# nano24rf.net
KiCad netlist of a schematic drawn in EAGLE
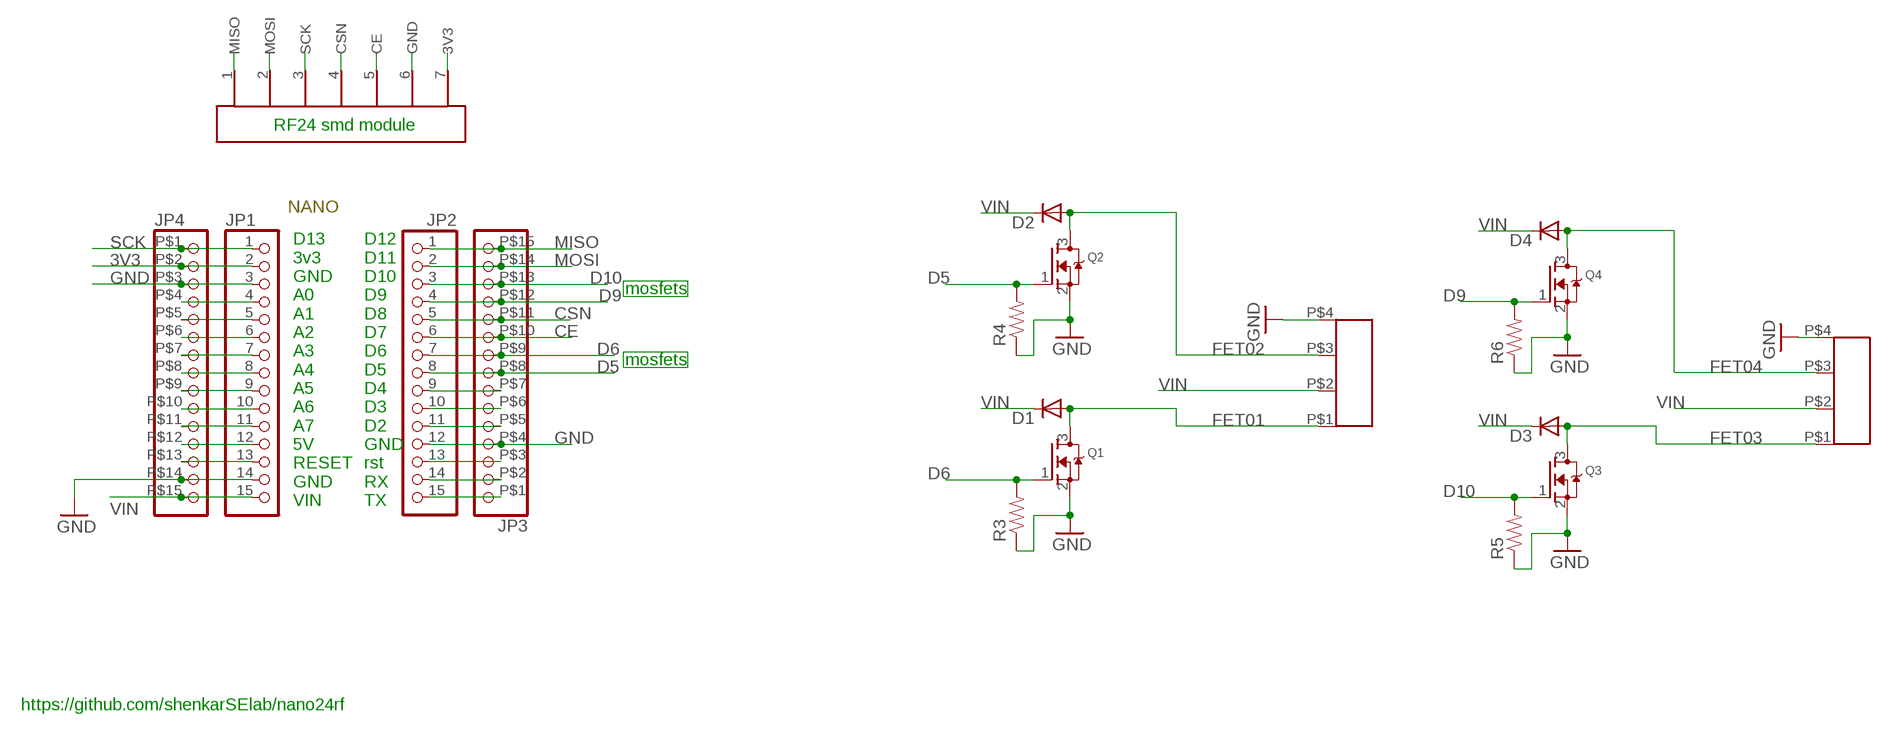
[diagram p0: schematic, sheet 1]

(export (version "E")
  (design (tool "Eeschema 10.0.6"))
  (components
    (comp (ref "D1")
      (value "DIODE-DO-214AC")
      (footprint "eagle-import:DO-214AC")
      (libsource (lib "eagle-import") (part "DIODE-DO-214AC"))
    )
    (comp (ref "D2")
      (value "DIODE-DO-214AC")
      (footprint "eagle-import:DO-214AC")
      (libsource (lib "eagle-import") (part "DIODE-DO-214AC"))
    )
    (comp (ref "D3")
      (value "DIODE-DO-214AC")
      (footprint "eagle-import:DO-214AC")
      (libsource (lib "eagle-import") (part "DIODE-DO-214AC"))
    )
    (comp (ref "D4")
      (value "DIODE-DO-214AC")
      (footprint "eagle-import:DO-214AC")
      (libsource (lib "eagle-import") (part "DIODE-DO-214AC"))
    )
    (comp (ref "JP1")
      (value "HEADER-1X15RND")
      (footprint "eagle-import:1X15_ROUND_70")
      (libsource (lib "eagle-import") (part "HEADER-1X15RND"))
    )
    (comp (ref "JP2")
      (value "HEADER-1X15RND")
      (footprint "eagle-import:1X15_ROUND_70")
      (libsource (lib "eagle-import") (part "HEADER-1X15RND"))
    )
    (comp (ref "JP3")
      (value "HEADER-1X15LONG")
      (footprint "eagle-import:1X15_LONG")
      (libsource (lib "eagle-import") (part "HEADER-1X15LONG"))
    )
    (comp (ref "JP4")
      (value "HEADER-1X15LONG")
      (footprint "eagle-import:1X15_LONG")
      (libsource (lib "eagle-import") (part "HEADER-1X15LONG"))
    )
    (comp (ref "MOSFET-12")
      (value "FATPAD4LONG")
      (footprint "eagle-import:FATFAD4-LONG")
      (libsource (lib "eagle-import") (part "FATPAD4LONG"))
    )
    (comp (ref "MOSFET-34")
      (value "FATPAD4LONG")
      (footprint "eagle-import:FATFAD4-LONG")
      (libsource (lib "eagle-import") (part "FATPAD4LONG"))
    )
    (comp (ref "Q1")
      (value "MOSFET-NWAVE")
      (footprint "eagle-import:SOT23-W")
      (libsource (lib "eagle-import") (part "MOSFET-NWAVE"))
    )
    (comp (ref "Q2")
      (value "MOSFET-NWAVE")
      (footprint "eagle-import:SOT23-W")
      (libsource (lib "eagle-import") (part "MOSFET-NWAVE"))
    )
    (comp (ref "Q3")
      (value "MOSFET-NWAVE")
      (footprint "eagle-import:SOT23-W")
      (libsource (lib "eagle-import") (part "MOSFET-NWAVE"))
    )
    (comp (ref "Q4")
      (value "MOSFET-NWAVE")
      (footprint "eagle-import:SOT23-W")
      (libsource (lib "eagle-import") (part "MOSFET-NWAVE"))
    )
    (comp (ref "R3")
      (value "RESISTOR0805-RES")
      (footprint "eagle-import:0805")
      (libsource (lib "eagle-import") (part "RESISTOR0805-RES"))
    )
    (comp (ref "R4")
      (value "RESISTOR0805-RES")
      (footprint "eagle-import:0805")
      (libsource (lib "eagle-import") (part "RESISTOR0805-RES"))
    )
    (comp (ref "R5")
      (value "RESISTOR0805-RES")
      (footprint "eagle-import:0805")
      (libsource (lib "eagle-import") (part "RESISTOR0805-RES"))
    )
    (comp (ref "R6")
      (value "RESISTOR0805-RES")
      (footprint "eagle-import:0805")
      (libsource (lib "eagle-import") (part "RESISTOR0805-RES"))
    )
    (comp (ref "RF24")
      (value "1X7-SMDPADS")
      (footprint "eagle-import:SMD1,27-2,54")
      (libsource (lib "eagle-import") (part "1X7-SMDPADS"))
    )
  )
  (nets
    (net (code "1") (name "3V3") (class "Default")
      (node (ref "JP1") (pin "2") (pinfunction "2_2") (pintype "passive"))
      (node (ref "JP4") (pin "P$2") (pinfunction "2_P$2") (pintype "passive"))
      (node (ref "RF24") (pin "7") (pinfunction "3V3_7") (pintype "bidirectional"))
    )
    (net (code "2") (name "CE") (class "Default")
      (node (ref "JP2") (pin "6") (pinfunction "6_6") (pintype "passive"))
      (node (ref "JP3") (pin "P$10") (pinfunction "10_P$10") (pintype "passive"))
      (node (ref "RF24") (pin "5") (pinfunction "CE_5") (pintype "bidirectional"))
    )
    (net (code "3") (name "CSN") (class "Default")
      (node (ref "JP2") (pin "5") (pinfunction "5_5") (pintype "passive"))
      (node (ref "JP3") (pin "P$11") (pinfunction "11_P$11") (pintype "passive"))
      (node (ref "RF24") (pin "4") (pinfunction "CSN_4") (pintype "bidirectional"))
    )
    (net (code "4") (name "D5") (class "Default")
      (node (ref "JP2") (pin "8") (pinfunction "8_8") (pintype "passive"))
      (node (ref "JP3") (pin "P$8") (pinfunction "8_P$8") (pintype "passive"))
      (node (ref "Q2") (pin "1") (pinfunction "G_1") (pintype "bidirectional"))
      (node (ref "R4") (pin "2") (pinfunction "2_2") (pintype "passive"))
    )
    (net (code "5") (name "D6") (class "Default")
      (node (ref "JP2") (pin "7") (pinfunction "7_7") (pintype "passive"))
      (node (ref "JP3") (pin "P$9") (pinfunction "9_P$9") (pintype "passive"))
      (node (ref "Q1") (pin "1") (pinfunction "G_1") (pintype "bidirectional"))
      (node (ref "R3") (pin "2") (pinfunction "2_2") (pintype "passive"))
    )
    (net (code "6") (name "D9") (class "Default")
      (node (ref "JP2") (pin "4") (pinfunction "4_4") (pintype "passive"))
      (node (ref "JP3") (pin "P$12") (pinfunction "12_P$12") (pintype "passive"))
      (node (ref "Q4") (pin "1") (pinfunction "G_1") (pintype "bidirectional"))
      (node (ref "R6") (pin "2") (pinfunction "2_2") (pintype "passive"))
    )
    (net (code "7") (name "D10") (class "Default")
      (node (ref "JP2") (pin "3") (pinfunction "3_3") (pintype "passive"))
      (node (ref "JP3") (pin "P$13") (pinfunction "13_P$13") (pintype "passive"))
      (node (ref "Q3") (pin "1") (pinfunction "G_1") (pintype "bidirectional"))
      (node (ref "R5") (pin "2") (pinfunction "2_2") (pintype "passive"))
    )
    (net (code "8") (name "FET01") (class "Default")
      (node (ref "D1") (pin "2") (pinfunction "A_2") (pintype "passive"))
      (node (ref "MOSFET-12") (pin "P$1") (pinfunction "P$1_P$1") (pintype "bidirectional"))
      (node (ref "Q1") (pin "3") (pinfunction "D_3") (pintype "bidirectional"))
    )
    (net (code "9") (name "FET02") (class "Default")
      (node (ref "D2") (pin "2") (pinfunction "A_2") (pintype "passive"))
      (node (ref "MOSFET-12") (pin "P$3") (pinfunction "P$3_P$3") (pintype "bidirectional"))
      (node (ref "Q2") (pin "3") (pinfunction "D_3") (pintype "bidirectional"))
    )
    (net (code "10") (name "FET03") (class "Default")
      (node (ref "D3") (pin "2") (pinfunction "A_2") (pintype "passive"))
      (node (ref "MOSFET-34") (pin "P$1") (pinfunction "P$1_P$1") (pintype "bidirectional"))
      (node (ref "Q3") (pin "3") (pinfunction "D_3") (pintype "bidirectional"))
    )
    (net (code "11") (name "FET04") (class "Default")
      (node (ref "D4") (pin "2") (pinfunction "A_2") (pintype "passive"))
      (node (ref "MOSFET-34") (pin "P$3") (pinfunction "P$3_P$3") (pintype "bidirectional"))
      (node (ref "Q4") (pin "3") (pinfunction "D_3") (pintype "bidirectional"))
    )
    (net (code "12") (name "GND") (class "Default")
      (node (ref "JP1") (pin "14") (pinfunction "14_14") (pintype "passive"))
      (node (ref "JP1") (pin "3") (pinfunction "3_3") (pintype "passive"))
      (node (ref "JP2") (pin "12") (pinfunction "12_12") (pintype "passive"))
      (node (ref "JP3") (pin "P$4") (pinfunction "4_P$4") (pintype "passive"))
      (node (ref "JP4") (pin "P$14") (pinfunction "14_P$14") (pintype "passive"))
      (node (ref "JP4") (pin "P$3") (pinfunction "3_P$3") (pintype "passive"))
      (node (ref "MOSFET-12") (pin "P$4") (pinfunction "P$4_P$4") (pintype "bidirectional"))
      (node (ref "MOSFET-34") (pin "P$4") (pinfunction "P$4_P$4") (pintype "bidirectional"))
      (node (ref "Q1") (pin "2") (pinfunction "S_2") (pintype "bidirectional"))
      (node (ref "Q2") (pin "2") (pinfunction "S_2") (pintype "bidirectional"))
      (node (ref "Q3") (pin "2") (pinfunction "S_2") (pintype "bidirectional"))
      (node (ref "Q4") (pin "2") (pinfunction "S_2") (pintype "bidirectional"))
      (node (ref "R3") (pin "1") (pinfunction "1_1") (pintype "passive"))
      (node (ref "R4") (pin "1") (pinfunction "1_1") (pintype "passive"))
      (node (ref "R5") (pin "1") (pinfunction "1_1") (pintype "passive"))
      (node (ref "R6") (pin "1") (pinfunction "1_1") (pintype "passive"))
      (node (ref "RF24") (pin "6") (pinfunction "GND_6") (pintype "bidirectional"))
    )
    (net (code "13") (name "MISO") (class "Default")
      (node (ref "JP2") (pin "1") (pinfunction "1_1") (pintype "passive"))
      (node (ref "JP3") (pin "P$15") (pinfunction "15_P$15") (pintype "passive"))
      (node (ref "RF24") (pin "1") (pinfunction "MISO_1") (pintype "bidirectional"))
    )
    (net (code "14") (name "MOSI") (class "Default")
      (node (ref "JP2") (pin "2") (pinfunction "2_2") (pintype "passive"))
      (node (ref "JP3") (pin "P$14") (pinfunction "14_P$14") (pintype "passive"))
      (node (ref "RF24") (pin "2") (pinfunction "MOSI_2") (pintype "bidirectional"))
    )
    (net (code "15") (name "Net-(JP3-1)") (class "Default")
      (node (ref "JP2") (pin "15") (pinfunction "15_15") (pintype "passive"))
      (node (ref "JP3") (pin "P$1") (pinfunction "1_P$1") (pintype "passive"))
    )
    (net (code "16") (name "Net-(JP3-2)") (class "Default")
      (node (ref "JP2") (pin "14") (pinfunction "14_14") (pintype "passive"))
      (node (ref "JP3") (pin "P$2") (pinfunction "2_P$2") (pintype "passive"))
    )
    (net (code "17") (name "Net-(JP3-3)") (class "Default")
      (node (ref "JP2") (pin "13") (pinfunction "13_13") (pintype "passive"))
      (node (ref "JP3") (pin "P$3") (pinfunction "3_P$3") (pintype "passive"))
    )
    (net (code "18") (name "Net-(JP3-5)") (class "Default")
      (node (ref "JP2") (pin "11") (pinfunction "11_11") (pintype "passive"))
      (node (ref "JP3") (pin "P$5") (pinfunction "5_P$5") (pintype "passive"))
    )
    (net (code "19") (name "Net-(JP3-6)") (class "Default")
      (node (ref "JP2") (pin "10") (pinfunction "10_10") (pintype "passive"))
      (node (ref "JP3") (pin "P$6") (pinfunction "6_P$6") (pintype "passive"))
    )
    (net (code "20") (name "Net-(JP3-7)") (class "Default")
      (node (ref "JP2") (pin "9") (pinfunction "9_9") (pintype "passive"))
      (node (ref "JP3") (pin "P$7") (pinfunction "7_P$7") (pintype "passive"))
    )
    (net (code "21") (name "Net-(JP4-4)") (class "Default")
      (node (ref "JP1") (pin "4") (pinfunction "4_4") (pintype "passive"))
      (node (ref "JP4") (pin "P$4") (pinfunction "4_P$4") (pintype "passive"))
    )
    (net (code "22") (name "Net-(JP4-5)") (class "Default")
      (node (ref "JP1") (pin "5") (pinfunction "5_5") (pintype "passive"))
      (node (ref "JP4") (pin "P$5") (pinfunction "5_P$5") (pintype "passive"))
    )
    (net (code "23") (name "Net-(JP4-6)") (class "Default")
      (node (ref "JP1") (pin "6") (pinfunction "6_6") (pintype "passive"))
      (node (ref "JP4") (pin "P$6") (pinfunction "6_P$6") (pintype "passive"))
    )
    (net (code "24") (name "Net-(JP4-7)") (class "Default")
      (node (ref "JP1") (pin "7") (pinfunction "7_7") (pintype "passive"))
      (node (ref "JP4") (pin "P$7") (pinfunction "7_P$7") (pintype "passive"))
    )
    (net (code "25") (name "Net-(JP4-8)") (class "Default")
      (node (ref "JP1") (pin "8") (pinfunction "8_8") (pintype "passive"))
      (node (ref "JP4") (pin "P$8") (pinfunction "8_P$8") (pintype "passive"))
    )
    (net (code "26") (name "Net-(JP4-9)") (class "Default")
      (node (ref "JP1") (pin "9") (pinfunction "9_9") (pintype "passive"))
      (node (ref "JP4") (pin "P$9") (pinfunction "9_P$9") (pintype "passive"))
    )
    (net (code "27") (name "Net-(JP4-10)") (class "Default")
      (node (ref "JP1") (pin "10") (pinfunction "10_10") (pintype "passive"))
      (node (ref "JP4") (pin "P$10") (pinfunction "10_P$10") (pintype "passive"))
    )
    (net (code "28") (name "Net-(JP4-11)") (class "Default")
      (node (ref "JP1") (pin "11") (pinfunction "11_11") (pintype "passive"))
      (node (ref "JP4") (pin "P$11") (pinfunction "11_P$11") (pintype "passive"))
    )
    (net (code "29") (name "Net-(JP4-12)") (class "Default")
      (node (ref "JP1") (pin "12") (pinfunction "12_12") (pintype "passive"))
      (node (ref "JP4") (pin "P$12") (pinfunction "12_P$12") (pintype "passive"))
    )
    (net (code "30") (name "Net-(JP4-13)") (class "Default")
      (node (ref "JP1") (pin "13") (pinfunction "13_13") (pintype "passive"))
      (node (ref "JP4") (pin "P$13") (pinfunction "13_P$13") (pintype "passive"))
    )
    (net (code "31") (name "SCK") (class "Default")
      (node (ref "JP1") (pin "1") (pinfunction "1_1") (pintype "passive"))
      (node (ref "JP4") (pin "P$1") (pinfunction "1_P$1") (pintype "passive"))
      (node (ref "RF24") (pin "3") (pinfunction "SCK_3") (pintype "bidirectional"))
    )
    (net (code "32") (name "VIN") (class "Default")
      (node (ref "D1") (pin "1") (pinfunction "C_1") (pintype "passive"))
      (node (ref "D2") (pin "1") (pinfunction "C_1") (pintype "passive"))
      (node (ref "D3") (pin "1") (pinfunction "C_1") (pintype "passive"))
      (node (ref "D4") (pin "1") (pinfunction "C_1") (pintype "passive"))
      (node (ref "JP1") (pin "15") (pinfunction "15_15") (pintype "passive"))
      (node (ref "JP4") (pin "P$15") (pinfunction "15_P$15") (pintype "passive"))
      (node (ref "MOSFET-12") (pin "P$2") (pinfunction "P$2_P$2") (pintype "bidirectional"))
      (node (ref "MOSFET-34") (pin "P$2") (pinfunction "P$2_P$2") (pintype "bidirectional"))
    )
  )
)
